# single_peg_board.net
KiCad netlist of a schematic drawn in EAGLE
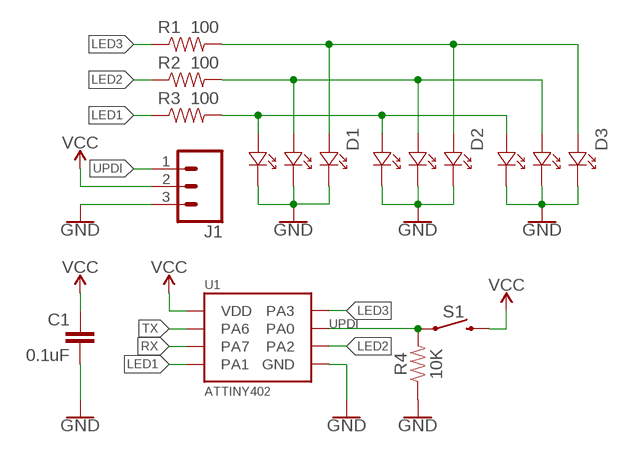
[diagram p0: schematic, sheet 1]

(export (version "E")
  (design (tool "Eeschema 10.0.6"))
  (components
    (comp (ref "C1")
      (value "0.1uF")
      (footprint "eagle-import:0603")
      (libsource (lib "eagle-import") (part "0.1UF-0603-25V-(+80/-20%)"))
    )
    (comp (ref "D1")
      (value "19-337C/RSBHGHC-A88/4T")
      (footprint "eagle-import:6-SMD")
      (libsource (lib "eagle-import") (part "19-337C/RSBHGHC-A88/4T"))
    )
    (comp (ref "D2")
      (value "19-337C/RSBHGHC-A88/4T")
      (footprint "eagle-import:6-SMD")
      (libsource (lib "eagle-import") (part "19-337C/RSBHGHC-A88/4T"))
    )
    (comp (ref "D3")
      (value "19-337C/RSBHGHC-A88/4T")
      (footprint "eagle-import:6-SMD")
      (libsource (lib "eagle-import") (part "19-337C/RSBHGHC-A88/4T"))
    )
    (comp (ref "J1")
      (value "CONN_03LONGPADS")
      (footprint "eagle-import:1X03_LONGPADS")
      (libsource (lib "eagle-import") (part "CONN_03LONGPADS"))
    )
    (comp (ref "R1")
      (value "100")
      (footprint "eagle-import:0603")
      (libsource (lib "eagle-import") (part "100OHM-0603-1/4W-5%"))
    )
    (comp (ref "R2")
      (value "100")
      (footprint "eagle-import:0603")
      (libsource (lib "eagle-import") (part "100OHM-0603-1/4W-5%"))
    )
    (comp (ref "R3")
      (value "100")
      (footprint "eagle-import:0603")
      (libsource (lib "eagle-import") (part "100OHM-0603-1/4W-5%"))
    )
    (comp (ref "R4")
      (value "10K")
      (footprint "eagle-import:0603")
      (libsource (lib "eagle-import") (part "100OHM-0603-1/4W-5%"))
    )
    (comp (ref "S1")
      (value "MOMENTARY-SWITCH-SPST-SMD-4.5MM-WINGED")
      (footprint "eagle-import:TACTILE_SWITCH_SMD_4.5MM_WINGED")
      (libsource (lib "eagle-import") (part "MOMENTARY-SWITCH-SPST-SMD-4.5MM-WINGED"))
    )
    (comp (ref "U1")
      (value "ATTINY402")
      (footprint "eagle-import:8-SOIC")
      (libsource (lib "eagle-import") (part "ATTINY402"))
    )
  )
  (nets
    (net (code "1") (name "GND") (class "Default")
      (node (ref "C1") (pin "2") (pinfunction "2_2") (pintype "passive"))
      (node (ref "D1") (pin "P$1") (pinfunction "P$1_P$1") (pintype "bidirectional"))
      (node (ref "D1") (pin "P$3") (pinfunction "P$3_P$3") (pintype "bidirectional"))
      (node (ref "D1") (pin "P$5") (pinfunction "P$5_P$5") (pintype "bidirectional"))
      (node (ref "D2") (pin "P$1") (pinfunction "P$1_P$1") (pintype "bidirectional"))
      (node (ref "D2") (pin "P$3") (pinfunction "P$3_P$3") (pintype "bidirectional"))
      (node (ref "D2") (pin "P$5") (pinfunction "P$5_P$5") (pintype "bidirectional"))
      (node (ref "D3") (pin "P$1") (pinfunction "P$1_P$1") (pintype "bidirectional"))
      (node (ref "D3") (pin "P$3") (pinfunction "P$3_P$3") (pintype "bidirectional"))
      (node (ref "D3") (pin "P$5") (pinfunction "P$5_P$5") (pintype "bidirectional"))
      (node (ref "J1") (pin "3") (pinfunction "3_3") (pintype "passive"))
      (node (ref "R4") (pin "1") (pinfunction "1_1") (pintype "passive"))
      (node (ref "U1") (pin "P$8") (pinfunction "GND_P$8") (pintype "bidirectional"))
    )
    (net (code "2") (name "LED1") (class "Default")
      (node (ref "R3") (pin "1") (pinfunction "1_1") (pintype "passive"))
      (node (ref "U1") (pin "P$4") (pinfunction "PA1_P$4") (pintype "bidirectional"))
    )
    (net (code "3") (name "LED2") (class "Default")
      (node (ref "R2") (pin "1") (pinfunction "1_1") (pintype "passive"))
      (node (ref "U1") (pin "P$5") (pinfunction "PA2_P$5") (pintype "bidirectional"))
    )
    (net (code "4") (name "LED3") (class "Default")
      (node (ref "R1") (pin "1") (pinfunction "1_1") (pintype "passive"))
      (node (ref "U1") (pin "P$7") (pinfunction "PA3_P$7") (pintype "bidirectional"))
    )
    (net (code "5") (name "Net-(D1-PadP$2)") (class "Default")
      (node (ref "D1") (pin "P$2") (pinfunction "P$2_P$2") (pintype "bidirectional"))
      (node (ref "D2") (pin "P$2") (pinfunction "P$2_P$2") (pintype "bidirectional"))
      (node (ref "D3") (pin "P$2") (pinfunction "P$2_P$2") (pintype "bidirectional"))
      (node (ref "R1") (pin "2") (pinfunction "2_2") (pintype "passive"))
    )
    (net (code "6") (name "Net-(D1-PadP$4)") (class "Default")
      (node (ref "D1") (pin "P$4") (pinfunction "P$4_P$4") (pintype "bidirectional"))
      (node (ref "D2") (pin "P$4") (pinfunction "P$4_P$4") (pintype "bidirectional"))
      (node (ref "D3") (pin "P$4") (pinfunction "P$4_P$4") (pintype "bidirectional"))
      (node (ref "R2") (pin "2") (pinfunction "2_2") (pintype "passive"))
    )
    (net (code "7") (name "Net-(D1-PadP$6)") (class "Default")
      (node (ref "D1") (pin "P$6") (pinfunction "P$6_P$6") (pintype "bidirectional"))
      (node (ref "D2") (pin "P$6") (pinfunction "P$6_P$6") (pintype "bidirectional"))
      (node (ref "D3") (pin "P$6") (pinfunction "P$6_P$6") (pintype "bidirectional"))
      (node (ref "R3") (pin "2") (pinfunction "2_2") (pintype "passive"))
    )
    (net (code "8") (name "RX") (class "Default")
      (node (ref "U1") (pin "P$3") (pinfunction "PA7_P$3") (pintype "bidirectional"))
    )
    (net (code "9") (name "TX") (class "Default")
      (node (ref "U1") (pin "P$2") (pinfunction "PA6_P$2") (pintype "bidirectional"))
    )
    (net (code "10") (name "UPDI") (class "Default")
      (node (ref "J1") (pin "1") (pinfunction "1_1") (pintype "passive"))
      (node (ref "R4") (pin "2") (pinfunction "2_2") (pintype "passive"))
      (node (ref "S1") (pin "2") (pinfunction "1_2") (pintype "passive"))
      (node (ref "S1") (pin "3") (pinfunction "1_3") (pintype "passive"))
      (node (ref "U1") (pin "P$6") (pinfunction "PA0_P$6") (pintype "bidirectional"))
    )
    (net (code "11") (name "VCC") (class "Default")
      (node (ref "C1") (pin "1") (pinfunction "1_1") (pintype "passive"))
      (node (ref "J1") (pin "2") (pinfunction "2_2") (pintype "passive"))
      (node (ref "S1") (pin "1") (pinfunction "2_1") (pintype "passive"))
      (node (ref "S1") (pin "4") (pinfunction "2_4") (pintype "passive"))
      (node (ref "U1") (pin "P$1") (pinfunction "VDD_P$1") (pintype "bidirectional"))
    )
  )
)
